# main.net
KiCad netlist of a schematic drawn in Altium Designer
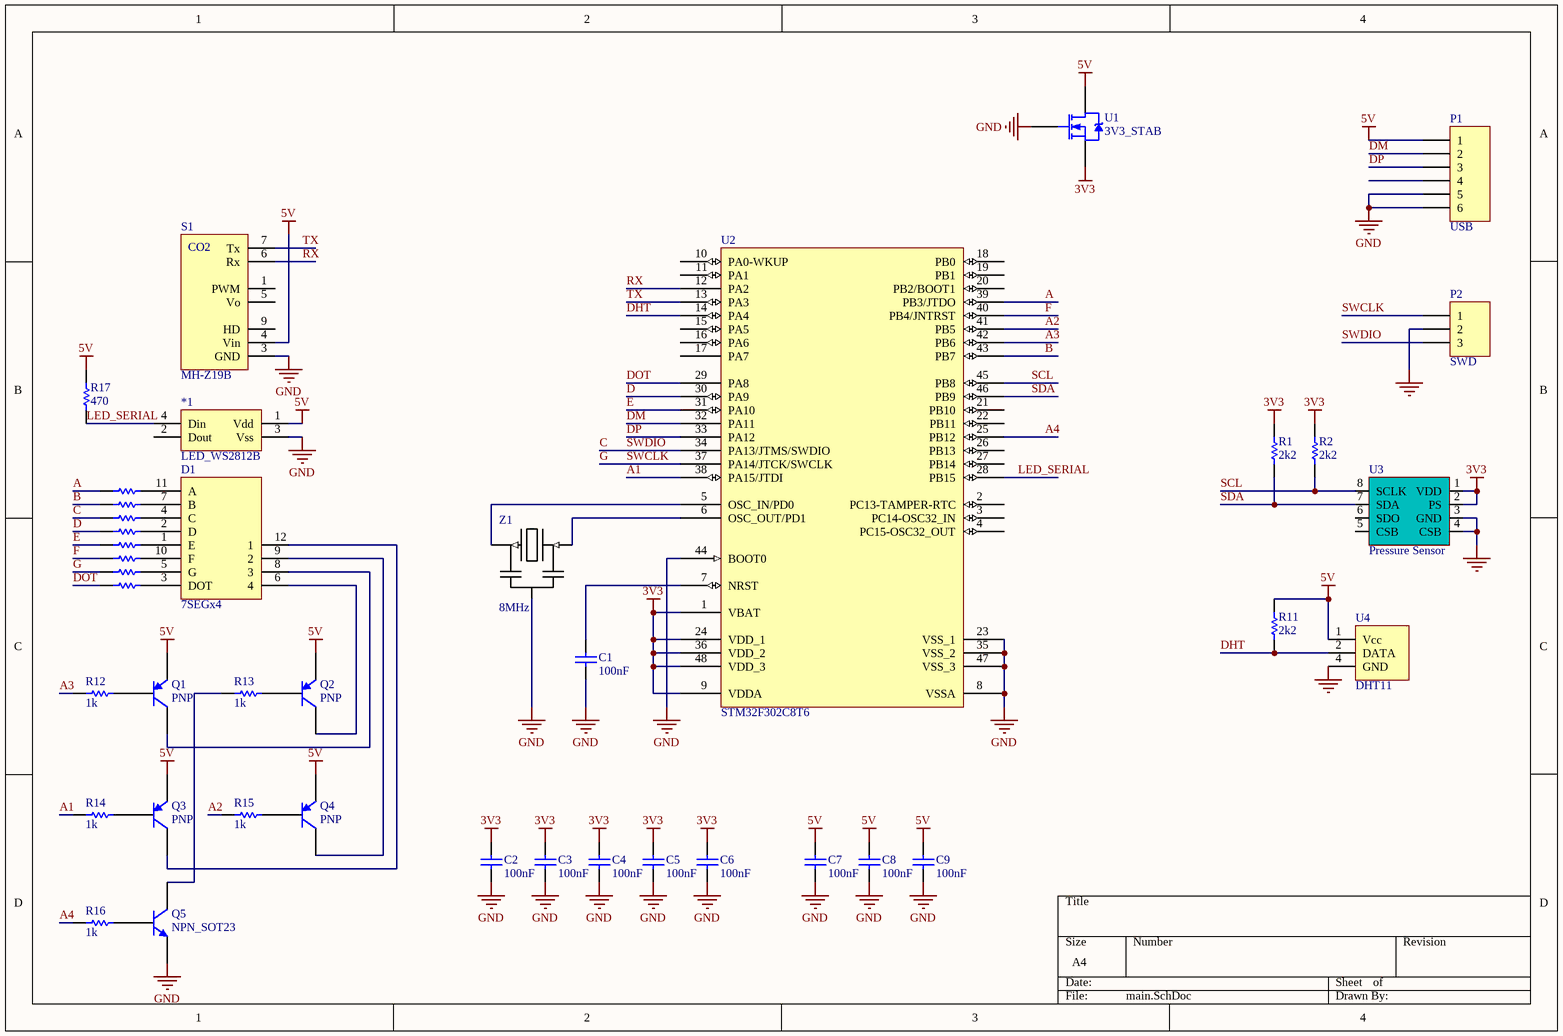
[diagram p0: main.SchDoc]

(export (version "E")
  (design (tool "Eeschema 10.0.6"))
  (components
    (comp (ref "*1")
      (value "LED_WS2812B")
      (footprint "LED_WS2812b")
      (libsource (lib "EDDLib") (part "LED_WS2812B"))
    )
    (comp (ref "C1")
      (value "100nF")
      (footprint "RC_0603")
      (description "Capacitor")
      (libsource (lib "Miscellaneous Devices") (part "Cap"))
    )
    (comp (ref "C2")
      (value "100nF")
      (footprint "RC_0603")
      (description "Capacitor")
      (libsource (lib "Miscellaneous Devices") (part "Cap"))
    )
    (comp (ref "C3")
      (value "100nF")
      (footprint "RC_0603")
      (description "Capacitor")
      (libsource (lib "Miscellaneous Devices") (part "Cap"))
    )
    (comp (ref "C4")
      (value "100nF")
      (footprint "RC_0603")
      (description "Capacitor")
      (libsource (lib "Miscellaneous Devices") (part "Cap"))
    )
    (comp (ref "C5")
      (value "100nF")
      (footprint "RC_0603")
      (description "Capacitor")
      (libsource (lib "Miscellaneous Devices") (part "Cap"))
    )
    (comp (ref "C6")
      (value "100nF")
      (footprint "RC_0603")
      (description "Capacitor")
      (libsource (lib "Miscellaneous Devices") (part "Cap"))
    )
    (comp (ref "C7")
      (value "100nF")
      (footprint "RC_0603")
      (description "Capacitor")
      (libsource (lib "Miscellaneous Devices") (part "Cap"))
    )
    (comp (ref "C8")
      (value "100nF")
      (footprint "RC_0603")
      (description "Capacitor")
      (libsource (lib "Miscellaneous Devices") (part "Cap"))
    )
    (comp (ref "C9")
      (value "100nF")
      (footprint "RC_0603")
      (description "Capacitor")
      (libsource (lib "Miscellaneous Devices") (part "Cap"))
    )
    (comp (ref "D1") (value "7SEGx4") (footprint "7SEG_4X_MEDIUM") (libsource (lib "EDDLib") (part "7SEGx4")))
    (comp (ref "P1")
      (value "USB")
      (footprint "RR_USB_MICRO_#1")
      (description "Header, 6-Pin")
      (fields (field (name "PUBLISHER") "Altium Limited"))
      (libsource (lib "Miscellaneous Connectors") (part "Header 6"))
    )
    (comp (ref "P2")
      (value "SWD")
      (footprint "MHDR1X3")
      (description "Header, 3-Pin")
      (fields (field (name "PUBLISHER") "Altium Limited"))
      (libsource (lib "Miscellaneous Connectors") (part "Header 3"))
    )
    (comp (ref "Q1")
      (value "PNP")
      (footprint "SOT-23B_L")
      (description "PNP Bipolar Transistor")
      (fields (field (name "PUBLISHER") "Altium Limited"))
      (libsource (lib "EDDLib") (part "PNP_SOT23"))
    )
    (comp (ref "Q2")
      (value "PNP")
      (footprint "SOT-23B_L")
      (description "PNP Bipolar Transistor")
      (fields (field (name "PUBLISHER") "Altium Limited"))
      (libsource (lib "EDDLib") (part "PNP_SOT23"))
    )
    (comp (ref "Q3")
      (value "PNP")
      (footprint "SOT-23B_L")
      (description "PNP Bipolar Transistor")
      (fields (field (name "PUBLISHER") "Altium Limited"))
      (libsource (lib "EDDLib") (part "PNP_SOT23"))
    )
    (comp (ref "Q4")
      (value "PNP")
      (footprint "SOT-23B_L")
      (description "PNP Bipolar Transistor")
      (fields (field (name "PUBLISHER") "Altium Limited"))
      (libsource (lib "EDDLib") (part "PNP_SOT23"))
    )
    (comp (ref "Q5")
      (value "NPN_SOT23")
      (footprint "SOT-23B_L")
      (description "NPN Bipolar Transistor")
      (fields (field (name "PUBLISHER") "Altium Limited"))
      (libsource (lib "EDDLib") (part "NPN_SOT23"))
    )
    (comp (ref "R1")
      (value "2k2")
      (footprint "RR_0603")
      (description "Resistor")
      (libsource (lib "Miscellaneous Devices") (part "Res1"))
    )
    (comp (ref "R2")
      (value "2k2")
      (footprint "RR_0603")
      (description "Resistor")
      (libsource (lib "Miscellaneous Devices") (part "Res1"))
    )
    (comp (ref "R3")
      (value "220")
      (footprint "RR_0603")
      (description "Resistor")
      (libsource (lib "Miscellaneous Devices") (part "Res1"))
    )
    (comp (ref "R4")
      (value "220")
      (footprint "RR_0603")
      (description "Resistor")
      (libsource (lib "Miscellaneous Devices") (part "Res1"))
    )
    (comp (ref "R5")
      (value "220")
      (footprint "RR_0603")
      (description "Resistor")
      (libsource (lib "Miscellaneous Devices") (part "Res1"))
    )
    (comp (ref "R6")
      (value "220")
      (footprint "RR_0603")
      (description "Resistor")
      (libsource (lib "Miscellaneous Devices") (part "Res1"))
    )
    (comp (ref "R7")
      (value "220")
      (footprint "RR_0603")
      (description "Resistor")
      (libsource (lib "Miscellaneous Devices") (part "Res1"))
    )
    (comp (ref "R8")
      (value "220")
      (footprint "RR_0603")
      (description "Resistor")
      (libsource (lib "Miscellaneous Devices") (part "Res1"))
    )
    (comp (ref "R9")
      (value "220")
      (footprint "RR_0603")
      (description "Resistor")
      (libsource (lib "Miscellaneous Devices") (part "Res1"))
    )
    (comp (ref "R10")
      (value "220")
      (footprint "RR_0603")
      (description "Resistor")
      (libsource (lib "Miscellaneous Devices") (part "Res1"))
    )
    (comp (ref "R11")
      (value "2k2")
      (footprint "RR_0603")
      (description "Resistor")
      (libsource (lib "Miscellaneous Devices") (part "Res1"))
    )
    (comp (ref "R12")
      (value "1k")
      (footprint "RR_0603")
      (description "Resistor")
      (libsource (lib "Miscellaneous Devices") (part "Res1"))
    )
    (comp (ref "R13")
      (value "1k")
      (footprint "RR_0603")
      (description "Resistor")
      (libsource (lib "Miscellaneous Devices") (part "Res1"))
    )
    (comp (ref "R14")
      (value "1k")
      (footprint "RR_0603")
      (description "Resistor")
      (libsource (lib "Miscellaneous Devices") (part "Res1"))
    )
    (comp (ref "R15")
      (value "1k")
      (footprint "RR_0603")
      (description "Resistor")
      (libsource (lib "Miscellaneous Devices") (part "Res1"))
    )
    (comp (ref "R16")
      (value "1k")
      (footprint "RR_0603")
      (description "Resistor")
      (libsource (lib "Miscellaneous Devices") (part "Res1"))
    )
    (comp (ref "R17")
      (value "470")
      (footprint "RR_0603")
      (description "Resistor")
      (libsource (lib "Miscellaneous Devices") (part "Res1"))
    )
    (comp (ref "S1") (value "MH-Z19B") (footprint "MH_Z19B") (libsource (lib "EDDLib") (part "MH_Z19B")))
    (comp (ref "U1")
      (value "3V3_STAB")
      (footprint "RR_SOT-23")
      (description "MOSFET N-CH 20V 4.2A SOT-23-3")
      (fields (field (name "MANUFACTURER") "Infineon Technologies"))
      (libsource (lib "RozumLibrary") (part "IRLML2502"))
    )
    (comp (ref "U2")
      (value "STM32F302C8T6")
      (footprint "LQFP48_N")
      (fields (field (name "PUBLISHER") "Altium Limited"))
      (libsource (lib "EDDLib") (part "STM32F302C8T6"))
    )
    (comp (ref "U3")
      (value "Pressure Sensor")
      (footprint "MS5611-01BA03")
      (description "Pressure Sensor - MS5611-01BA03")
      (libsource (lib "OpenPilot") (part "MS5611-01BA03"))
    )
    (comp (ref "U4") (value "DHT11") (footprint "DHT11") (libsource (lib "EDDLib") (part "DHT11")))
    (comp (ref "Z1")
      (value "8MHz")
      (footprint "RR_CRYSTAL_3.2X1.3")
      (description "XTAL 8.0000MHZ 33PF SMD")
      (fields (field (name "MANUFACTURER") "Murata Electronics"))
      (libsource (lib "EDDLib") (part "CSTCE8M00G55-R0"))
    )
  )
  (nets
    (net (code "1") (name "/A") (class "Default")
      (node (ref "R3") (pin "1") (pinfunction "1_1") (pintype "passive"))
      (node (ref "U2") (pin "39") (pinfunction "PB3/JTDO_39") (pintype "bidirectional"))
    )
    (net (code "2") (name "/A1") (class "Default")
      (node (ref "R14") (pin "1") (pinfunction "1_1") (pintype "passive"))
      (node (ref "U2") (pin "38") (pinfunction "PA15/JTDI_38") (pintype "bidirectional"))
    )
    (net (code "3") (name "/A2") (class "Default")
      (node (ref "R15") (pin "1") (pinfunction "1_1") (pintype "passive"))
      (node (ref "U2") (pin "41") (pinfunction "PB5_41") (pintype "bidirectional"))
    )
    (net (code "4") (name "/A3") (class "Default")
      (node (ref "R12") (pin "1") (pinfunction "1_1") (pintype "passive"))
      (node (ref "U2") (pin "42") (pinfunction "PB6_42") (pintype "bidirectional"))
    )
    (net (code "5") (name "/A4") (class "Default")
      (node (ref "R16") (pin "1") (pinfunction "1_1") (pintype "passive"))
      (node (ref "U2") (pin "25") (pinfunction "PB12_25") (pintype "bidirectional"))
    )
    (net (code "6") (name "/B") (class "Default")
      (node (ref "R4") (pin "1") (pinfunction "1_1") (pintype "passive"))
      (node (ref "U2") (pin "43") (pinfunction "PB7_43") (pintype "bidirectional"))
    )
    (net (code "7") (name "/C") (class "Default")
      (node (ref "P2") (pin "3") (pinfunction "3_3") (pintype "passive"))
      (node (ref "R5") (pin "1") (pinfunction "1_1") (pintype "passive"))
      (node (ref "U2") (pin "34") (pinfunction "PA13/JTMS/SWDIO_34") (pintype "passive"))
    )
    (net (code "8") (name "/D") (class "Default")
      (node (ref "R6") (pin "1") (pinfunction "1_1") (pintype "passive"))
      (node (ref "U2") (pin "30") (pinfunction "PA9_30") (pintype "bidirectional"))
    )
    (net (code "9") (name "/DHT") (class "Default")
      (node (ref "R11") (pin "1") (pinfunction "1_1") (pintype "passive"))
      (node (ref "U2") (pin "14") (pinfunction "PA4_14") (pintype "bidirectional"))
      (node (ref "U4") (pin "2") (pinfunction "DATA_2") (pintype "passive"))
    )
    (net (code "10") (name "/DM") (class "Default")
      (node (ref "P1") (pin "2") (pinfunction "2_2") (pintype "passive"))
      (node (ref "U2") (pin "32") (pinfunction "PA11_32") (pintype "passive"))
    )
    (net (code "11") (name "/DOT") (class "Default")
      (node (ref "R10") (pin "1") (pinfunction "1_1") (pintype "passive"))
      (node (ref "U2") (pin "29") (pinfunction "PA8_29") (pintype "passive"))
    )
    (net (code "12") (name "/DP") (class "Default")
      (node (ref "P1") (pin "3") (pinfunction "3_3") (pintype "passive"))
      (node (ref "U2") (pin "33") (pinfunction "PA12_33") (pintype "passive"))
    )
    (net (code "13") (name "/E") (class "Default")
      (node (ref "R7") (pin "1") (pinfunction "1_1") (pintype "passive"))
      (node (ref "U2") (pin "31") (pinfunction "PA10_31") (pintype "bidirectional"))
    )
    (net (code "14") (name "/F") (class "Default")
      (node (ref "R8") (pin "1") (pinfunction "1_1") (pintype "passive"))
      (node (ref "U2") (pin "40") (pinfunction "PB4/JNTRST_40") (pintype "bidirectional"))
    )
    (net (code "15") (name "/G") (class "Default")
      (node (ref "P2") (pin "1") (pinfunction "1_1") (pintype "passive"))
      (node (ref "R9") (pin "1") (pinfunction "1_1") (pintype "passive"))
      (node (ref "U2") (pin "37") (pinfunction "PA14/JTCK/SWCLK_37") (pintype "passive"))
    )
    (net (code "16") (name "/LED_SERIAL") (class "Default")
      (node (ref "*1") (pin "4") (pinfunction "Din_4") (pintype "passive"))
      (node (ref "R17") (pin "1") (pinfunction "1_1") (pintype "passive"))
      (node (ref "U2") (pin "28") (pinfunction "PB15_28") (pintype "bidirectional"))
    )
    (net (code "17") (name "/RX") (class "Default")
      (node (ref "S1") (pin "6") (pinfunction "Rx_6") (pintype "passive"))
      (node (ref "U2") (pin "12") (pinfunction "PA2_12") (pintype "passive"))
    )
    (net (code "18") (name "/SCL") (class "Default")
      (node (ref "R2") (pin "1") (pinfunction "1_1") (pintype "passive"))
      (node (ref "U2") (pin "45") (pinfunction "PB8_45") (pintype "bidirectional"))
      (node (ref "U3") (pin "8") (pinfunction "SCLK_8") (pintype "passive"))
    )
    (net (code "19") (name "/SDA") (class "Default")
      (node (ref "R1") (pin "1") (pinfunction "1_1") (pintype "passive"))
      (node (ref "U2") (pin "46") (pinfunction "PB9_46") (pintype "bidirectional"))
      (node (ref "U3") (pin "7") (pinfunction "SDA_7") (pintype "passive"))
    )
    (net (code "20") (name "/TX") (class "Default")
      (node (ref "S1") (pin "7") (pinfunction "Tx_7") (pintype "passive"))
      (node (ref "U2") (pin "13") (pinfunction "PA3_13") (pintype "bidirectional"))
    )
    (net (code "21") (name "3V3") (class "Default")
      (node (ref "C2") (pin "2") (pinfunction "2_2") (pintype "passive"))
      (node (ref "C3") (pin "2") (pinfunction "2_2") (pintype "passive"))
      (node (ref "C4") (pin "2") (pinfunction "2_2") (pintype "passive"))
      (node (ref "C5") (pin "2") (pinfunction "2_2") (pintype "passive"))
      (node (ref "C6") (pin "2") (pinfunction "2_2") (pintype "passive"))
      (node (ref "R1") (pin "2") (pinfunction "2_2") (pintype "passive"))
      (node (ref "R2") (pin "2") (pinfunction "2_2") (pintype "passive"))
      (node (ref "U1") (pin "2") (pinfunction "S_2") (pintype "passive"))
      (node (ref "U2") (pin "1") (pinfunction "VBAT_1") (pintype "power_in"))
      (node (ref "U2") (pin "24") (pinfunction "VDD_1_24") (pintype "power_in"))
      (node (ref "U2") (pin "36") (pinfunction "VDD_2_36") (pintype "power_in"))
      (node (ref "U2") (pin "48") (pinfunction "VDD_3_48") (pintype "power_in"))
      (node (ref "U2") (pin "9") (pinfunction "VDDA_9") (pintype "power_in"))
      (node (ref "U3") (pin "1") (pinfunction "VDD_1") (pintype "power_in"))
      (node (ref "U3") (pin "2") (pinfunction "PS_2") (pintype "passive"))
    )
    (net (code "22") (name "5V") (class "Default")
      (node (ref "*1") (pin "1") (pinfunction "Vdd_1") (pintype "passive"))
      (node (ref "C7") (pin "2") (pinfunction "2_2") (pintype "passive"))
      (node (ref "C8") (pin "2") (pinfunction "2_2") (pintype "passive"))
      (node (ref "C9") (pin "2") (pinfunction "2_2") (pintype "passive"))
      (node (ref "P1") (pin "1") (pinfunction "1_1") (pintype "passive"))
      (node (ref "Q1") (pin "2") (pinfunction "E_2") (pintype "passive"))
      (node (ref "Q2") (pin "2") (pinfunction "E_2") (pintype "passive"))
      (node (ref "Q3") (pin "2") (pinfunction "E_2") (pintype "passive"))
      (node (ref "Q4") (pin "2") (pinfunction "E_2") (pintype "passive"))
      (node (ref "R11") (pin "2") (pinfunction "2_2") (pintype "passive"))
      (node (ref "R17") (pin "2") (pinfunction "2_2") (pintype "passive"))
      (node (ref "S1") (pin "4") (pinfunction "Vin_4") (pintype "passive"))
      (node (ref "U1") (pin "3") (pinfunction "D_3") (pintype "passive"))
      (node (ref "U4") (pin "1") (pinfunction "Vcc_1") (pintype "passive"))
    )
    (net (code "23") (name "GND") (class "Default")
      (node (ref "*1") (pin "3") (pinfunction "Vss_3") (pintype "passive"))
      (node (ref "C1") (pin "1") (pinfunction "1_1") (pintype "passive"))
      (node (ref "C2") (pin "1") (pinfunction "1_1") (pintype "passive"))
      (node (ref "C3") (pin "1") (pinfunction "1_1") (pintype "passive"))
      (node (ref "C4") (pin "1") (pinfunction "1_1") (pintype "passive"))
      (node (ref "C5") (pin "1") (pinfunction "1_1") (pintype "passive"))
      (node (ref "C6") (pin "1") (pinfunction "1_1") (pintype "passive"))
      (node (ref "C7") (pin "1") (pinfunction "1_1") (pintype "passive"))
      (node (ref "C8") (pin "1") (pinfunction "1_1") (pintype "passive"))
      (node (ref "C9") (pin "1") (pinfunction "1_1") (pintype "passive"))
      (node (ref "P1") (pin "5") (pinfunction "5_5") (pintype "passive"))
      (node (ref "P1") (pin "6") (pinfunction "6_6") (pintype "passive"))
      (node (ref "P2") (pin "2") (pinfunction "2_2") (pintype "passive"))
      (node (ref "Q5") (pin "2") (pinfunction "E_2") (pintype "passive"))
      (node (ref "S1") (pin "3") (pinfunction "GND_3") (pintype "passive"))
      (node (ref "U1") (pin "1") (pinfunction "G_1") (pintype "passive"))
      (node (ref "U2") (pin "23") (pinfunction "VSS_1_23") (pintype "power_in"))
      (node (ref "U2") (pin "35") (pinfunction "VSS_2_35") (pintype "power_in"))
      (node (ref "U2") (pin "44") (pinfunction "BOOT0_44") (pintype "input"))
      (node (ref "U2") (pin "47") (pinfunction "VSS_3_47") (pintype "power_in"))
      (node (ref "U2") (pin "8") (pinfunction "VSSA_8") (pintype "power_in"))
      (node (ref "U3") (pin "3") (pinfunction "GND_3") (pintype "power_in"))
      (node (ref "U3") (pin "4") (pinfunction "CSB_4") (pintype "passive"))
      (node (ref "U4") (pin "4") (pinfunction "GND_4") (pintype "passive"))
      (node (ref "Z1") (pin "2") (pinfunction "GND_2") (pintype "passive"))
    )
    (net (code "24") (name "Net-(D1-1)") (class "Default")
      (node (ref "D1") (pin "12") (pinfunction "1_12") (pintype "passive"))
      (node (ref "Q3") (pin "3") (pinfunction "C_3") (pintype "passive"))
    )
    (net (code "25") (name "Net-(D1-2)") (class "Default")
      (node (ref "D1") (pin "9") (pinfunction "2_9") (pintype "passive"))
      (node (ref "Q4") (pin "3") (pinfunction "C_3") (pintype "passive"))
    )
    (net (code "26") (name "Net-(D1-3)") (class "Default")
      (node (ref "D1") (pin "8") (pinfunction "3_8") (pintype "passive"))
      (node (ref "Q1") (pin "3") (pinfunction "C_3") (pintype "passive"))
    )
    (net (code "27") (name "Net-(D1-4)") (class "Default")
      (node (ref "D1") (pin "6") (pinfunction "4_6") (pintype "passive"))
      (node (ref "Q2") (pin "3") (pinfunction "C_3") (pintype "passive"))
    )
    (net (code "28") (name "Net-(D1-A)") (class "Default")
      (node (ref "D1") (pin "11") (pinfunction "A_11") (pintype "passive"))
      (node (ref "R3") (pin "2") (pinfunction "2_2") (pintype "passive"))
    )
    (net (code "29") (name "Net-(D1-B)") (class "Default")
      (node (ref "D1") (pin "7") (pinfunction "B_7") (pintype "passive"))
      (node (ref "R4") (pin "2") (pinfunction "2_2") (pintype "passive"))
    )
    (net (code "30") (name "Net-(D1-C)") (class "Default")
      (node (ref "D1") (pin "4") (pinfunction "C_4") (pintype "passive"))
      (node (ref "R5") (pin "2") (pinfunction "2_2") (pintype "passive"))
    )
    (net (code "31") (name "Net-(D1-D)") (class "Default")
      (node (ref "D1") (pin "2") (pinfunction "D_2") (pintype "passive"))
      (node (ref "R6") (pin "2") (pinfunction "2_2") (pintype "passive"))
    )
    (net (code "32") (name "Net-(D1-DOT)") (class "Default")
      (node (ref "D1") (pin "3") (pinfunction "DOT_3") (pintype "passive"))
      (node (ref "R10") (pin "2") (pinfunction "2_2") (pintype "passive"))
    )
    (net (code "33") (name "Net-(D1-E)") (class "Default")
      (node (ref "D1") (pin "1") (pinfunction "E_1") (pintype "passive"))
      (node (ref "R7") (pin "2") (pinfunction "2_2") (pintype "passive"))
    )
    (net (code "34") (name "Net-(D1-F)") (class "Default")
      (node (ref "D1") (pin "10") (pinfunction "F_10") (pintype "passive"))
      (node (ref "R8") (pin "2") (pinfunction "2_2") (pintype "passive"))
    )
    (net (code "35") (name "Net-(D1-G)") (class "Default")
      (node (ref "D1") (pin "5") (pinfunction "G_5") (pintype "passive"))
      (node (ref "R9") (pin "2") (pinfunction "2_2") (pintype "passive"))
    )
    (net (code "36") (name "Net-(Q1-B)") (class "Default")
      (node (ref "Q1") (pin "1") (pinfunction "B_1") (pintype "passive"))
      (node (ref "R12") (pin "2") (pinfunction "2_2") (pintype "passive"))
    )
    (net (code "37") (name "Net-(Q2-B)") (class "Default")
      (node (ref "Q2") (pin "1") (pinfunction "B_1") (pintype "passive"))
      (node (ref "R13") (pin "2") (pinfunction "2_2") (pintype "passive"))
    )
    (net (code "38") (name "Net-(Q3-B)") (class "Default")
      (node (ref "Q3") (pin "1") (pinfunction "B_1") (pintype "passive"))
      (node (ref "R14") (pin "2") (pinfunction "2_2") (pintype "passive"))
    )
    (net (code "39") (name "Net-(Q4-B)") (class "Default")
      (node (ref "Q4") (pin "1") (pinfunction "B_1") (pintype "passive"))
      (node (ref "R15") (pin "2") (pinfunction "2_2") (pintype "passive"))
    )
    (net (code "40") (name "Net-(Q5-B)") (class "Default")
      (node (ref "Q5") (pin "1") (pinfunction "B_1") (pintype "passive"))
      (node (ref "R16") (pin "2") (pinfunction "2_2") (pintype "passive"))
    )
    (net (code "41") (name "Net-(Q5-C)") (class "Default")
      (node (ref "Q5") (pin "3") (pinfunction "C_3") (pintype "passive"))
      (node (ref "R13") (pin "1") (pinfunction "1_1") (pintype "passive"))
    )
    (net (code "42") (name "Net-(U2-NRST)") (class "Default")
      (node (ref "C1") (pin "2") (pinfunction "2_2") (pintype "passive"))
      (node (ref "U2") (pin "7") (pinfunction "NRST_7") (pintype "bidirectional"))
    )
    (net (code "43") (name "Net-(U2-OSC_IN{slash}PD0)") (class "Default")
      (node (ref "U2") (pin "5") (pinfunction "OSC_IN/PD0_5") (pintype "passive"))
      (node (ref "Z1") (pin "1") (pinfunction "X1_1") (pintype "output"))
    )
    (net (code "44") (name "Net-(U2-OSC_OUT{slash}PD1)") (class "Default")
      (node (ref "U2") (pin "6") (pinfunction "OSC_OUT/PD1_6") (pintype "passive"))
      (node (ref "Z1") (pin "3") (pinfunction "X2_3") (pintype "input"))
    )
    (net (code "45") (name "unconnected-(*1-Dout-Pad2)") (class "Default")
      (node (ref "*1") (pin "2") (pinfunction "Dout_2") (pintype "passive"))
    )
    (net (code "46") (name "unconnected-(P1-Pad4)") (class "Default")
      (node (ref "P1") (pin "4") (pinfunction "4_4") (pintype "passive"))
    )
    (net (code "47") (name "unconnected-(S1-HD-Pad9)") (class "Default")
      (node (ref "S1") (pin "9") (pinfunction "HD_9") (pintype "passive"))
    )
    (net (code "48") (name "unconnected-(S1-PWM-Pad1)") (class "Default")
      (node (ref "S1") (pin "1") (pinfunction "PWM_1") (pintype "passive"))
    )
    (net (code "49") (name "unconnected-(S1-Vo-Pad5)") (class "Default")
      (node (ref "S1") (pin "5") (pinfunction "Vo_5") (pintype "passive"))
    )
    (net (code "50") (name "unconnected-(U2-PA0-WKUP-Pad10)") (class "Default")
      (node (ref "U2") (pin "10") (pinfunction "PA0-WKUP_10") (pintype "bidirectional"))
    )
    (net (code "51") (name "unconnected-(U2-PA1-Pad11)") (class "Default")
      (node (ref "U2") (pin "11") (pinfunction "PA1_11") (pintype "bidirectional"))
    )
    (net (code "52") (name "unconnected-(U2-PA5-Pad15)") (class "Default")
      (node (ref "U2") (pin "15") (pinfunction "PA5_15") (pintype "bidirectional"))
    )
    (net (code "53") (name "unconnected-(U2-PA6-Pad16)") (class "Default")
      (node (ref "U2") (pin "16") (pinfunction "PA6_16") (pintype "bidirectional"))
    )
    (net (code "54") (name "unconnected-(U2-PA7-Pad17)") (class "Default")
      (node (ref "U2") (pin "17") (pinfunction "PA7_17") (pintype "passive"))
    )
    (net (code "55") (name "unconnected-(U2-PB0-Pad18)") (class "Default")
      (node (ref "U2") (pin "18") (pinfunction "PB0_18") (pintype "bidirectional"))
    )
    (net (code "56") (name "unconnected-(U2-PB1-Pad19)") (class "Default")
      (node (ref "U2") (pin "19") (pinfunction "PB1_19") (pintype "bidirectional"))
    )
    (net (code "57") (name "unconnected-(U2-PB2{slash}BOOT1-Pad20)") (class "Default")
      (node (ref "U2") (pin "20") (pinfunction "PB2/BOOT1_20") (pintype "bidirectional"))
    )
    (net (code "58") (name "unconnected-(U2-PB10-Pad21)") (class "Default")
      (node (ref "U2") (pin "21") (pinfunction "PB10_21") (pintype "bidirectional"))
    )
    (net (code "59") (name "unconnected-(U2-PB11-Pad22)") (class "Default")
      (node (ref "U2") (pin "22") (pinfunction "PB11_22") (pintype "bidirectional"))
    )
    (net (code "60") (name "unconnected-(U2-PB13-Pad26)") (class "Default")
      (node (ref "U2") (pin "26") (pinfunction "PB13_26") (pintype "bidirectional"))
    )
    (net (code "61") (name "unconnected-(U2-PB14-Pad27)") (class "Default")
      (node (ref "U2") (pin "27") (pinfunction "PB14_27") (pintype "bidirectional"))
    )
    (net (code "62") (name "unconnected-(U2-PC13-TAMPER-RTC-Pad2)") (class "Default")
      (node (ref "U2") (pin "2") (pinfunction "PC13-TAMPER-RTC_2") (pintype "bidirectional"))
    )
    (net (code "63") (name "unconnected-(U2-PC14-OSC32_IN-Pad3)") (class "Default")
      (node (ref "U2") (pin "3") (pinfunction "PC14-OSC32_IN_3") (pintype "bidirectional"))
    )
    (net (code "64") (name "unconnected-(U2-PC15-OSC32_OUT-Pad4)") (class "Default")
      (node (ref "U2") (pin "4") (pinfunction "PC15-OSC32_OUT_4") (pintype "bidirectional"))
    )
    (net (code "65") (name "unconnected-(U3-CSB-Pad5)") (class "Default")
      (node (ref "U3") (pin "5") (pinfunction "CSB_5") (pintype "passive"))
    )
    (net (code "66") (name "unconnected-(U3-SDO-Pad6)") (class "Default")
      (node (ref "U3") (pin "6") (pinfunction "SDO_6") (pintype "passive"))
    )
  )
)
